# D1_CM.net
KiCad netlist of a schematic drawn in EAGLE
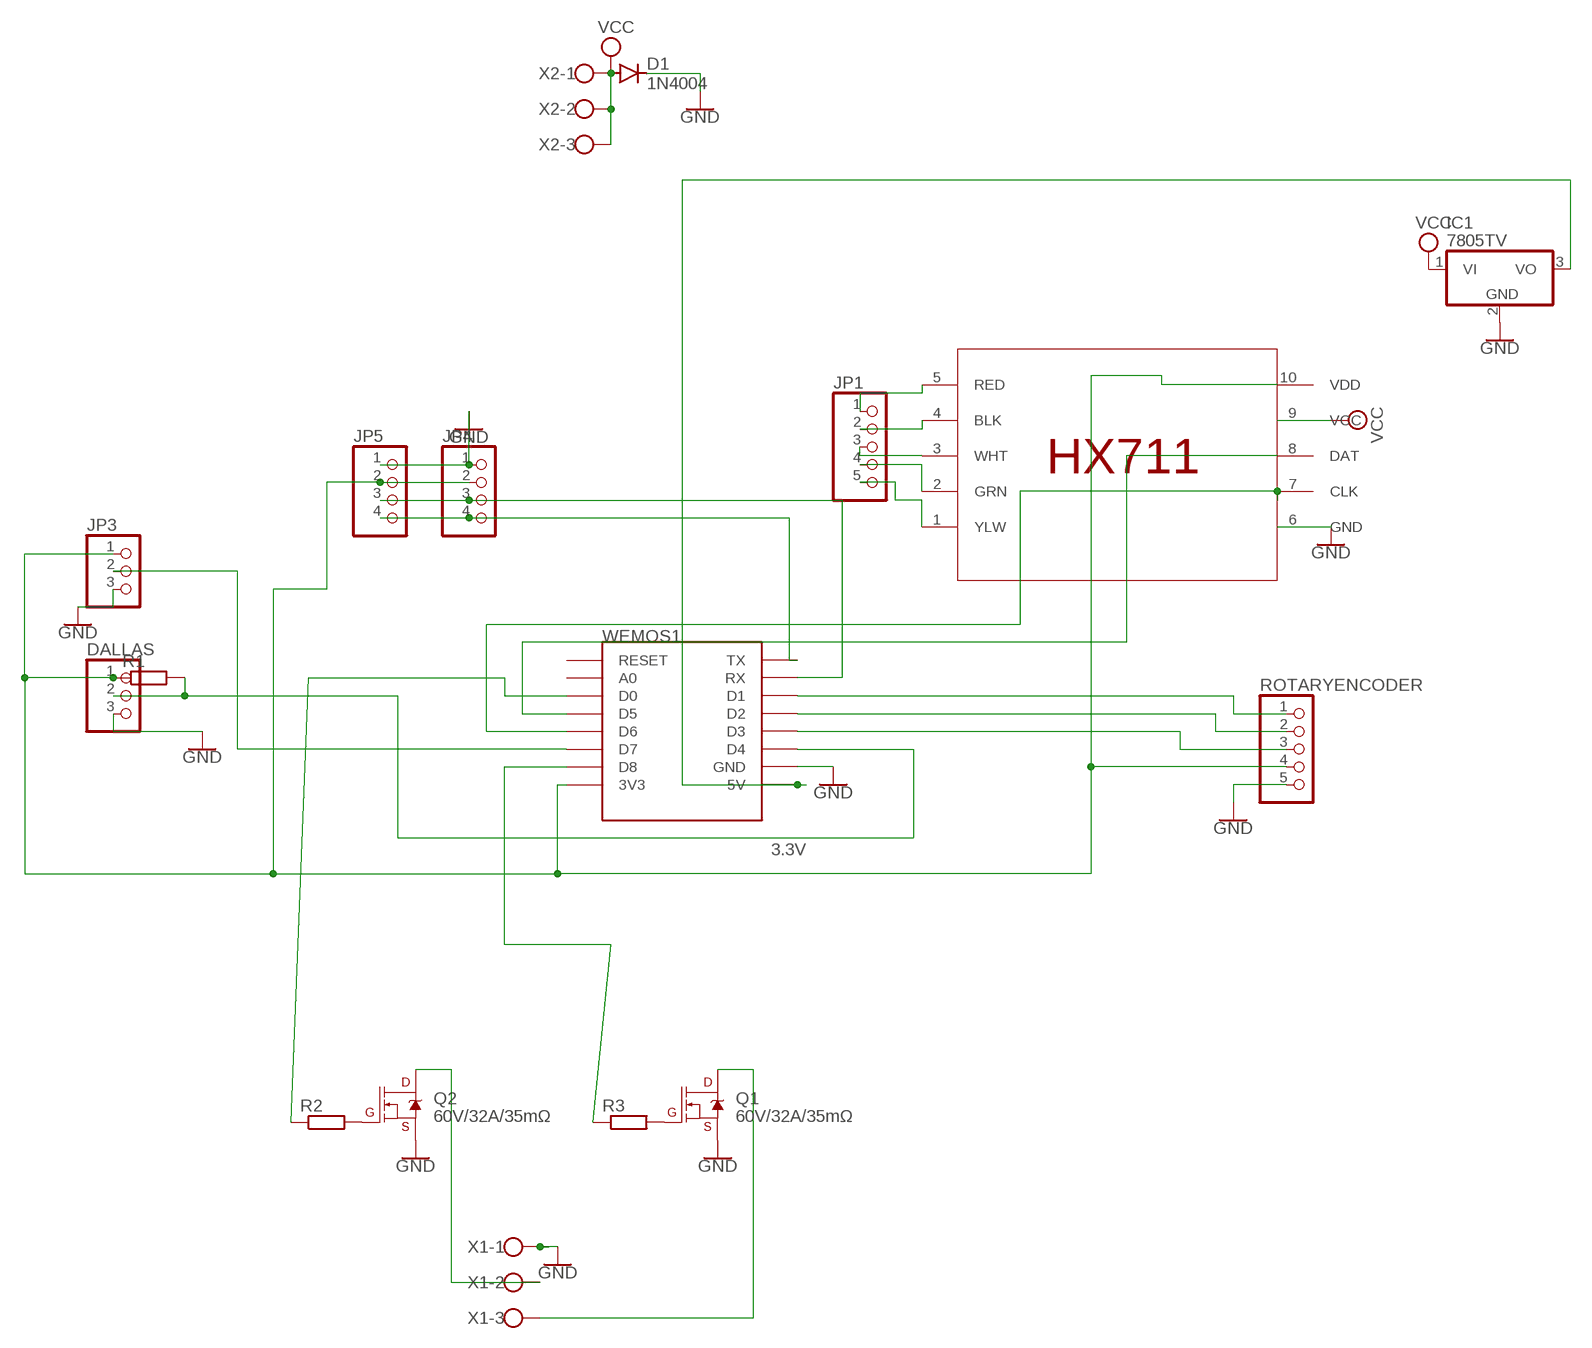
[diagram p0: schematic, sheet 1]

(export (version "E")
  (design (tool "Eeschema 10.0.6"))
  (components
    (comp (ref "D1")
      (value "1N4004")
      (footprint "eagle-import:DO41-10")
      (libsource (lib "eagle-import") (part "1N4004"))
    )
    (comp (ref "DALLAS")
      (value "PINHD-1X3")
      (footprint "eagle-import:1X03")
      (libsource (lib "eagle-import") (part "PINHD-1X3"))
    )
    (comp (ref "IC1")
      (value "7805TV")
      (footprint "eagle-import:TO220V")
      (libsource (lib "eagle-import") (part "78TV05"))
    )
    (comp (ref "JP1")
      (value "PINHD-1X5")
      (footprint "eagle-import:1X05")
      (libsource (lib "eagle-import") (part "PINHD-1X5"))
    )
    (comp (ref "JP3")
      (value "PINHD-1X3")
      (footprint "eagle-import:1X03")
      (libsource (lib "eagle-import") (part "PINHD-1X3"))
    )
    (comp (ref "JP4")
      (value "PINHD-1X4")
      (footprint "eagle-import:1X04")
      (libsource (lib "eagle-import") (part "PINHD-1X4"))
    )
    (comp (ref "JP5")
      (value "PINHD-1X4")
      (footprint "eagle-import:1X04")
      (libsource (lib "eagle-import") (part "PINHD-1X4"))
    )
    (comp (ref "Q1")
      (value "60V/32A/35mΩ")
      (footprint "eagle-import:TO220V")
      (libsource (lib "eagle-import") (part "MOSFET-NCH-FQP30N06L"))
    )
    (comp (ref "Q2")
      (value "60V/32A/35mΩ")
      (footprint "eagle-import:TO220V")
      (libsource (lib "eagle-import") (part "MOSFET-NCH-FQP30N06L"))
    )
    (comp (ref "R1")
      (value "R-EU_0207/7")
      (footprint "eagle-import:0207_7")
      (libsource (lib "eagle-import") (part "R-EU_0207/7"))
    )
    (comp (ref "R2")
      (value "R-EU_0207/7")
      (footprint "eagle-import:0207_7")
      (libsource (lib "eagle-import") (part "R-EU_0207/7"))
    )
    (comp (ref "R3")
      (value "R-EU_0207/7")
      (footprint "eagle-import:0207_7")
      (libsource (lib "eagle-import") (part "R-EU_0207/7"))
    )
    (comp (ref "ROTARYENCODER")
      (value "PINHD-1X5")
      (footprint "eagle-import:1X05")
      (libsource (lib "eagle-import") (part "PINHD-1X5"))
    )
    (comp (ref "U$1")
      (value "DEVICY")
      (footprint "eagle-import:FOOTSY")
      (libsource (lib "eagle-import") (part "DEVICY"))
    )
    (comp (ref "WEMOS1")
      (value "WEMOS-D1-MINI")
      (footprint "eagle-import:WEMOS-D1-MINI")
      (libsource (lib "eagle-import") (part "WEMOS-D1-MINI"))
    )
    (comp (ref "X1")
      (value "W237-103")
      (footprint "eagle-import:W237-103")
      (fields (field (name "MPN") "237-103"))
      (libsource (lib "eagle-import") (part "W237-103"))
    )
    (comp (ref "X2")
      (value "W237-103")
      (footprint "eagle-import:W237-103")
      (fields (field (name "MPN") "237-103"))
      (libsource (lib "eagle-import") (part "W237-103"))
    )
  )
  (nets
    (net (code "1") (name "/3.3V") (class "Default")
      (node (ref "DALLAS") (pin "1") (pinfunction "1_1") (pintype "passive"))
      (node (ref "JP3") (pin "1") (pinfunction "1_1") (pintype "passive"))
      (node (ref "JP4") (pin "2") (pinfunction "2_2") (pintype "passive"))
      (node (ref "JP5") (pin "2") (pinfunction "2_2") (pintype "passive"))
      (node (ref "R1") (pin "1") (pinfunction "1_1") (pintype "passive"))
      (node (ref "ROTARYENCODER") (pin "4") (pinfunction "4_4") (pintype "passive"))
      (node (ref "U$1") (pin "10") (pinfunction "VDD_10") (pintype "bidirectional"))
      (node (ref "WEMOS1") (pin "3V3") (pinfunction "3V3_3V3") (pintype "bidirectional"))
    )
    (net (code "2") (name "GND") (class "Default")
      (node (ref "D1") (pin "C") (pinfunction "C_C") (pintype "passive"))
      (node (ref "DALLAS") (pin "3") (pinfunction "3_3") (pintype "passive"))
      (node (ref "IC1") (pin "2") (pinfunction "GND_2") (pintype "passive"))
      (node (ref "JP3") (pin "3") (pinfunction "3_3") (pintype "passive"))
      (node (ref "JP4") (pin "1") (pinfunction "1_1") (pintype "passive"))
      (node (ref "JP5") (pin "1") (pinfunction "1_1") (pintype "passive"))
      (node (ref "Q1") (pin "3") (pinfunction "S_3") (pintype "bidirectional"))
      (node (ref "Q2") (pin "3") (pinfunction "S_3") (pintype "bidirectional"))
      (node (ref "ROTARYENCODER") (pin "5") (pinfunction "5_5") (pintype "passive"))
      (node (ref "U$1") (pin "6") (pinfunction "GND_6") (pintype "bidirectional"))
      (node (ref "WEMOS1") (pin "GND") (pinfunction "GND_GND") (pintype "bidirectional"))
      (node (ref "X1") (pin "1") (pinfunction "KL_1") (pintype "passive"))
    )
    (net (code "3") (name "Net-(DALLAS-Pad2)") (class "Default")
      (node (ref "DALLAS") (pin "2") (pinfunction "2_2") (pintype "passive"))
      (node (ref "R1") (pin "2") (pinfunction "2_2") (pintype "passive"))
      (node (ref "WEMOS1") (pin "D4") (pinfunction "D4_D4") (pintype "bidirectional"))
    )
    (net (code "4") (name "Net-(IC1-VO)") (class "Default")
      (node (ref "IC1") (pin "3") (pinfunction "VO_3") (pintype "passive"))
      (node (ref "WEMOS1") (pin "5V") (pinfunction "5V_5V") (pintype "bidirectional"))
    )
    (net (code "5") (name "Net-(JP3-Pad2)") (class "Default")
      (node (ref "JP3") (pin "2") (pinfunction "2_2") (pintype "passive"))
      (node (ref "WEMOS1") (pin "D7") (pinfunction "D7_D7") (pintype "bidirectional"))
    )
    (net (code "6") (name "Net-(JP4-Pad3)") (class "Default")
      (node (ref "JP4") (pin "3") (pinfunction "3_3") (pintype "passive"))
      (node (ref "JP5") (pin "3") (pinfunction "3_3") (pintype "passive"))
      (node (ref "WEMOS1") (pin "RX") (pinfunction "RX_RX") (pintype "bidirectional"))
    )
    (net (code "7") (name "Net-(JP4-Pad4)") (class "Default")
      (node (ref "JP4") (pin "4") (pinfunction "4_4") (pintype "passive"))
      (node (ref "JP5") (pin "4") (pinfunction "4_4") (pintype "passive"))
      (node (ref "WEMOS1") (pin "TX") (pinfunction "TX_TX") (pintype "bidirectional"))
    )
    (net (code "8") (name "Net-(Q1-D)") (class "Default")
      (node (ref "Q1") (pin "2") (pinfunction "D_2") (pintype "bidirectional"))
      (node (ref "X1") (pin "3") (pinfunction "KL_3") (pintype "passive"))
    )
    (net (code "9") (name "Net-(Q1-G)") (class "Default")
      (node (ref "Q1") (pin "1") (pinfunction "G_1") (pintype "bidirectional"))
      (node (ref "R3") (pin "2") (pinfunction "2_2") (pintype "passive"))
    )
    (net (code "10") (name "Net-(Q2-D)") (class "Default")
      (node (ref "Q2") (pin "2") (pinfunction "D_2") (pintype "bidirectional"))
      (node (ref "X1") (pin "2") (pinfunction "KL_2") (pintype "passive"))
    )
    (net (code "11") (name "Net-(Q2-G)") (class "Default")
      (node (ref "Q2") (pin "1") (pinfunction "G_1") (pintype "bidirectional"))
      (node (ref "R2") (pin "2") (pinfunction "2_2") (pintype "passive"))
    )
    (net (code "12") (name "Net-(R2-Pad1)") (class "Default")
      (node (ref "R2") (pin "1") (pinfunction "1_1") (pintype "passive"))
      (node (ref "WEMOS1") (pin "D0") (pinfunction "D0_D0") (pintype "bidirectional"))
    )
    (net (code "13") (name "Net-(R3-Pad1)") (class "Default")
      (node (ref "R3") (pin "1") (pinfunction "1_1") (pintype "passive"))
      (node (ref "WEMOS1") (pin "D8") (pinfunction "D8_D8") (pintype "bidirectional"))
    )
    (net (code "14") (name "Net-(ROTARYENCODER-Pad1)") (class "Default")
      (node (ref "ROTARYENCODER") (pin "1") (pinfunction "1_1") (pintype "passive"))
      (node (ref "WEMOS1") (pin "D1") (pinfunction "D1_D1") (pintype "bidirectional"))
    )
    (net (code "15") (name "Net-(ROTARYENCODER-Pad2)") (class "Default")
      (node (ref "ROTARYENCODER") (pin "2") (pinfunction "2_2") (pintype "passive"))
      (node (ref "WEMOS1") (pin "D2") (pinfunction "D2_D2") (pintype "bidirectional"))
    )
    (net (code "16") (name "Net-(ROTARYENCODER-Pad3)") (class "Default")
      (node (ref "ROTARYENCODER") (pin "3") (pinfunction "3_3") (pintype "passive"))
      (node (ref "WEMOS1") (pin "D3") (pinfunction "D3_D3") (pintype "bidirectional"))
    )
    (net (code "17") (name "Net-(U$1-BLK)") (class "Default")
      (node (ref "JP1") (pin "2") (pinfunction "2_2") (pintype "passive"))
      (node (ref "U$1") (pin "4") (pinfunction "BLK_4") (pintype "bidirectional"))
    )
    (net (code "18") (name "Net-(U$1-CLK)") (class "Default")
      (node (ref "U$1") (pin "7") (pinfunction "CLK_7") (pintype "bidirectional"))
      (node (ref "WEMOS1") (pin "D6") (pinfunction "D6_D6") (pintype "bidirectional"))
    )
    (net (code "19") (name "Net-(U$1-DAT)") (class "Default")
      (node (ref "U$1") (pin "8") (pinfunction "DAT_8") (pintype "bidirectional"))
      (node (ref "WEMOS1") (pin "D5") (pinfunction "D5_D5") (pintype "bidirectional"))
    )
    (net (code "20") (name "Net-(U$1-GRN)") (class "Default")
      (node (ref "JP1") (pin "4") (pinfunction "4_4") (pintype "passive"))
      (node (ref "U$1") (pin "2") (pinfunction "GRN_2") (pintype "bidirectional"))
    )
    (net (code "21") (name "Net-(U$1-RED)") (class "Default")
      (node (ref "JP1") (pin "1") (pinfunction "1_1") (pintype "passive"))
      (node (ref "U$1") (pin "5") (pinfunction "RED_5") (pintype "bidirectional"))
    )
    (net (code "22") (name "Net-(U$1-WHT)") (class "Default")
      (node (ref "JP1") (pin "3") (pinfunction "3_3") (pintype "passive"))
      (node (ref "U$1") (pin "3") (pinfunction "WHT_3") (pintype "bidirectional"))
    )
    (net (code "23") (name "Net-(U$1-YLW)") (class "Default")
      (node (ref "JP1") (pin "5") (pinfunction "5_5") (pintype "passive"))
      (node (ref "U$1") (pin "1") (pinfunction "YLW_1") (pintype "bidirectional"))
    )
    (net (code "24") (name "VCC") (class "Default")
      (node (ref "D1") (pin "A") (pinfunction "A_A") (pintype "passive"))
      (node (ref "IC1") (pin "1") (pinfunction "VI_1") (pintype "input"))
      (node (ref "U$1") (pin "9") (pinfunction "VCC_9") (pintype "bidirectional"))
      (node (ref "X2") (pin "1") (pinfunction "KL_1") (pintype "passive"))
      (node (ref "X2") (pin "2") (pinfunction "KL_2") (pintype "passive"))
      (node (ref "X2") (pin "3") (pinfunction "KL_3") (pintype "passive"))
    )
    (net (code "25") (name "unconnected-(WEMOS1-PadA0)") (class "Default")
      (node (ref "WEMOS1") (pin "A0") (pinfunction "A0_A0") (pintype "bidirectional"))
    )
    (net (code "26") (name "unconnected-(WEMOS1-PadRESET)") (class "Default")
      (node (ref "WEMOS1") (pin "RESET") (pinfunction "RESET_RESET") (pintype "bidirectional"))
    )
  )
)
